# 3_TopLevel.net
KiCad netlist of a schematic drawn in Altium Designer
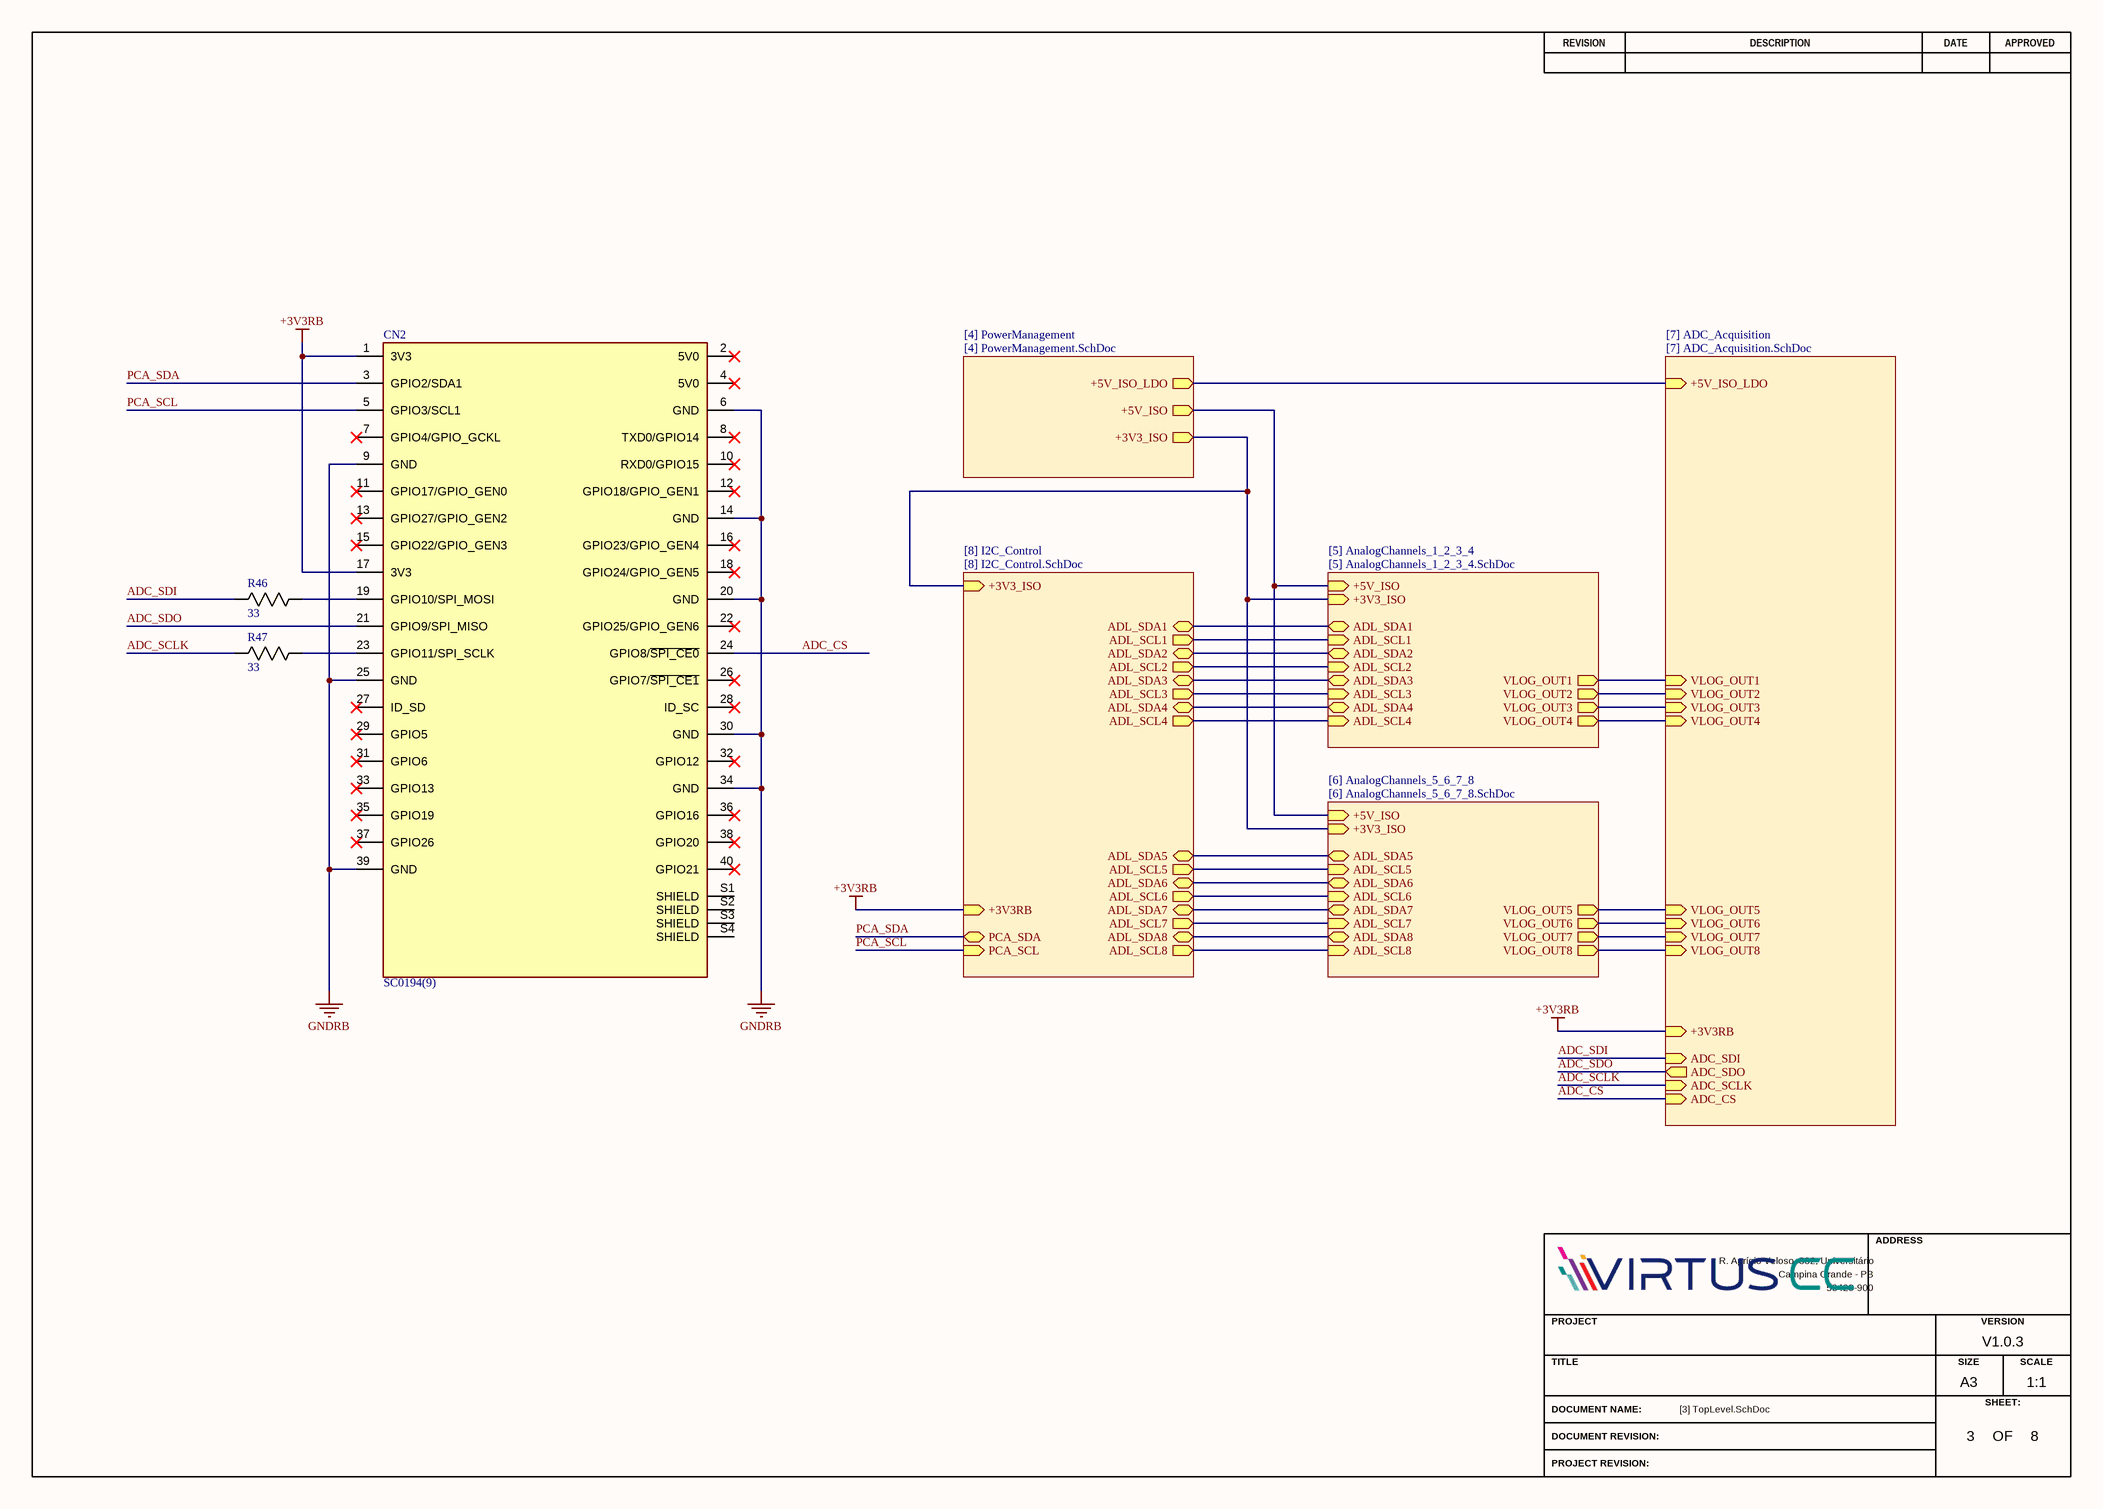
[diagram p0: [3] TopLevel.SchDoc]

(export (version "E")
  (design (tool "Eeschema 10.0.6"))
  (components
    (comp (ref "CN2")
      (value "SC0194(9)")
      (footprint "RPI_SHIELD_CONNECTOR")
      (fields (field (name "MF") "Raspberry Pi"))
      (libsource (lib "PCEIOT") (part "SC0194(9)"))
    )
    (comp (ref "R46")
      (value "33")
      (footprint "RESC1005X40N")
      (description "33 Ohms ±1% 0.063W, 1/16W Chip Resistor 0402 (1005 Metric) Moisture Resistant Thick Film")
      (fields
        (field (name "MANUFACTURER_PART_NUMBER") "RC0402FR-0733RL")
        (field (name "COPYRIGHT") "Copyright (C) 2025 Ultra Librarian. All rights reserved.")
      )
      (libsource (lib "PCEIOT") (part "RC0402FR-0733RL"))
    )
    (comp (ref "R47")
      (value "33")
      (footprint "RESC1005X40N")
      (description "33 Ohms ±1% 0.063W, 1/16W Chip Resistor 0402 (1005 Metric) Moisture Resistant Thick Film")
      (fields
        (field (name "MANUFACTURER_PART_NUMBER") "RC0402FR-0733RL")
        (field (name "COPYRIGHT") "Copyright (C) 2025 Ultra Librarian. All rights reserved.")
      )
      (libsource (lib "PCEIOT") (part "RC0402FR-0733RL"))
    )
  )
  (nets
    (net (code "1") (name "+3V3RB") (class "Default")
      (node (ref "CN2") (pin "1") (pinfunction "3V3_1") (pintype "passive"))
      (node (ref "CN2") (pin "17") (pinfunction "3V3_17") (pintype "passive"))
    )
    (net (code "5") (name "/ADC_CS") (class "Default")
      (node (ref "CN2") (pin "24") (pinfunction "GPIO8/~{SPI_CE0}_24") (pintype "passive"))
    )
    (net (code "6") (name "/ADC_SCLK") (class "Default")
      (node (ref "R47") (pin "2") (pinfunction "2_2") (pintype "passive"))
    )
    (net (code "7") (name "/ADC_SDI") (class "Default")
      (node (ref "R46") (pin "2") (pinfunction "2_2") (pintype "passive"))
    )
    (net (code "8") (name "/ADC_SDO") (class "Default")
      (node (ref "CN2") (pin "21") (pinfunction "GPIO9/SPI_MISO_21") (pintype "passive"))
    )
    (net (code "25") (name "/PCA_SCL") (class "Default")
      (node (ref "CN2") (pin "5") (pinfunction "GPIO3/SCL1_5") (pintype "passive"))
    )
    (net (code "26") (name "/PCA_SDA") (class "Default")
      (node (ref "CN2") (pin "3") (pinfunction "GPIO2/SDA1_3") (pintype "passive"))
    )
    (net (code "35") (name "GNDRB") (class "Default")
      (node (ref "CN2") (pin "14") (pinfunction "GND_14") (pintype "passive"))
      (node (ref "CN2") (pin "20") (pinfunction "GND_20") (pintype "passive"))
      (node (ref "CN2") (pin "25") (pinfunction "GND_25") (pintype "passive"))
      (node (ref "CN2") (pin "30") (pinfunction "GND_30") (pintype "passive"))
      (node (ref "CN2") (pin "34") (pinfunction "GND_34") (pintype "passive"))
      (node (ref "CN2") (pin "39") (pinfunction "GND_39") (pintype "passive"))
      (node (ref "CN2") (pin "6") (pinfunction "GND_6") (pintype "passive"))
      (node (ref "CN2") (pin "9") (pinfunction "GND_9") (pintype "passive"))
    )
    (net (code "36") (name "Net-(CN2-GPIO10{slash}SPI_MOSI)") (class "Default")
      (node (ref "CN2") (pin "19") (pinfunction "GPIO10/SPI_MOSI_19") (pintype "passive"))
      (node (ref "R46") (pin "1") (pinfunction "1_1") (pintype "passive"))
    )
    (net (code "37") (name "Net-(CN2-GPIO11{slash}SPI_SCLK)") (class "Default")
      (node (ref "CN2") (pin "23") (pinfunction "GPIO11/SPI_SCLK_23") (pintype "passive"))
      (node (ref "R47") (pin "1") (pinfunction "1_1") (pintype "passive"))
    )
    (net (code "38") (name "unconnected-(CN2-5V0-Pad2)") (class "Default")
      (node (ref "CN2") (pin "2") (pinfunction "5V0_2") (pintype "passive+no_connect"))
    )
    (net (code "39") (name "unconnected-(CN2-5V0-Pad4)") (class "Default")
      (node (ref "CN2") (pin "4") (pinfunction "5V0_4") (pintype "passive+no_connect"))
    )
    (net (code "40") (name "unconnected-(CN2-GPIO4{slash}GPIO_GCKL-Pad7)") (class "Default")
      (node (ref "CN2") (pin "7") (pinfunction "GPIO4/GPIO_GCKL_7") (pintype "passive+no_connect"))
    )
    (net (code "41") (name "unconnected-(CN2-GPIO5-Pad29)") (class "Default")
      (node (ref "CN2") (pin "29") (pinfunction "GPIO5_29") (pintype "passive+no_connect"))
    )
    (net (code "42") (name "unconnected-(CN2-GPIO6-Pad31)") (class "Default")
      (node (ref "CN2") (pin "31") (pinfunction "GPIO6_31") (pintype "passive+no_connect"))
    )
    (net (code "43") (name "unconnected-(CN2-GPIO7{slash}~{SPI_CE1}-Pad26)") (class "Default")
      (node (ref "CN2") (pin "26") (pinfunction "GPIO7/~{SPI_CE1}_26") (pintype "passive+no_connect"))
    )
    (net (code "44") (name "unconnected-(CN2-GPIO12-Pad32)") (class "Default")
      (node (ref "CN2") (pin "32") (pinfunction "GPIO12_32") (pintype "passive+no_connect"))
    )
    (net (code "45") (name "unconnected-(CN2-GPIO13-Pad33)") (class "Default")
      (node (ref "CN2") (pin "33") (pinfunction "GPIO13_33") (pintype "passive+no_connect"))
    )
    (net (code "46") (name "unconnected-(CN2-GPIO16-Pad36)") (class "Default")
      (node (ref "CN2") (pin "36") (pinfunction "GPIO16_36") (pintype "passive+no_connect"))
    )
    (net (code "47") (name "unconnected-(CN2-GPIO17{slash}GPIO_GEN0-Pad11)") (class "Default")
      (node (ref "CN2") (pin "11") (pinfunction "GPIO17/GPIO_GEN0_11") (pintype "passive+no_connect"))
    )
    (net (code "48") (name "unconnected-(CN2-GPIO18{slash}GPIO_GEN1-Pad12)") (class "Default")
      (node (ref "CN2") (pin "12") (pinfunction "GPIO18/GPIO_GEN1_12") (pintype "passive+no_connect"))
    )
    (net (code "49") (name "unconnected-(CN2-GPIO19-Pad35)") (class "Default")
      (node (ref "CN2") (pin "35") (pinfunction "GPIO19_35") (pintype "passive+no_connect"))
    )
    (net (code "50") (name "unconnected-(CN2-GPIO20-Pad38)") (class "Default")
      (node (ref "CN2") (pin "38") (pinfunction "GPIO20_38") (pintype "passive+no_connect"))
    )
    (net (code "51") (name "unconnected-(CN2-GPIO21-Pad40)") (class "Default")
      (node (ref "CN2") (pin "40") (pinfunction "GPIO21_40") (pintype "passive+no_connect"))
    )
    (net (code "52") (name "unconnected-(CN2-GPIO22{slash}GPIO_GEN3-Pad15)") (class "Default")
      (node (ref "CN2") (pin "15") (pinfunction "GPIO22/GPIO_GEN3_15") (pintype "passive+no_connect"))
    )
    (net (code "53") (name "unconnected-(CN2-GPIO23{slash}GPIO_GEN4-Pad16)") (class "Default")
      (node (ref "CN2") (pin "16") (pinfunction "GPIO23/GPIO_GEN4_16") (pintype "passive+no_connect"))
    )
    (net (code "54") (name "unconnected-(CN2-GPIO24{slash}GPIO_GEN5-Pad18)") (class "Default")
      (node (ref "CN2") (pin "18") (pinfunction "GPIO24/GPIO_GEN5_18") (pintype "passive+no_connect"))
    )
    (net (code "55") (name "unconnected-(CN2-GPIO25{slash}GPIO_GEN6-Pad22)") (class "Default")
      (node (ref "CN2") (pin "22") (pinfunction "GPIO25/GPIO_GEN6_22") (pintype "passive+no_connect"))
    )
    (net (code "56") (name "unconnected-(CN2-GPIO26-Pad37)") (class "Default")
      (node (ref "CN2") (pin "37") (pinfunction "GPIO26_37") (pintype "passive+no_connect"))
    )
    (net (code "57") (name "unconnected-(CN2-GPIO27{slash}GPIO_GEN2-Pad13)") (class "Default")
      (node (ref "CN2") (pin "13") (pinfunction "GPIO27/GPIO_GEN2_13") (pintype "passive+no_connect"))
    )
    (net (code "58") (name "unconnected-(CN2-ID_SC-Pad28)") (class "Default")
      (node (ref "CN2") (pin "28") (pinfunction "ID_SC_28") (pintype "passive+no_connect"))
    )
    (net (code "59") (name "unconnected-(CN2-ID_SD-Pad27)") (class "Default")
      (node (ref "CN2") (pin "27") (pinfunction "ID_SD_27") (pintype "passive+no_connect"))
    )
    (net (code "60") (name "unconnected-(CN2-RXD0{slash}GPIO15-Pad10)") (class "Default")
      (node (ref "CN2") (pin "10") (pinfunction "RXD0/GPIO15_10") (pintype "passive+no_connect"))
    )
    (net (code "61") (name "unconnected-(CN2-SHIELD-PadS1)") (class "Default")
      (node (ref "CN2") (pin "S1") (pinfunction "SHIELD_S1") (pintype "passive"))
    )
    (net (code "62") (name "unconnected-(CN2-SHIELD-PadS2)") (class "Default")
      (node (ref "CN2") (pin "S2") (pinfunction "SHIELD_S2") (pintype "passive"))
    )
    (net (code "63") (name "unconnected-(CN2-SHIELD-PadS3)") (class "Default")
      (node (ref "CN2") (pin "S3") (pinfunction "SHIELD_S3") (pintype "passive"))
    )
    (net (code "64") (name "unconnected-(CN2-SHIELD-PadS4)") (class "Default")
      (node (ref "CN2") (pin "S4") (pinfunction "SHIELD_S4") (pintype "passive"))
    )
    (net (code "65") (name "unconnected-(CN2-TXD0{slash}GPIO14-Pad8)") (class "Default")
      (node (ref "CN2") (pin "8") (pinfunction "TXD0/GPIO14_8") (pintype "passive+no_connect"))
    )
  )
)
